# openmv.net
KiCad netlist of a schematic drawn in EAGLE
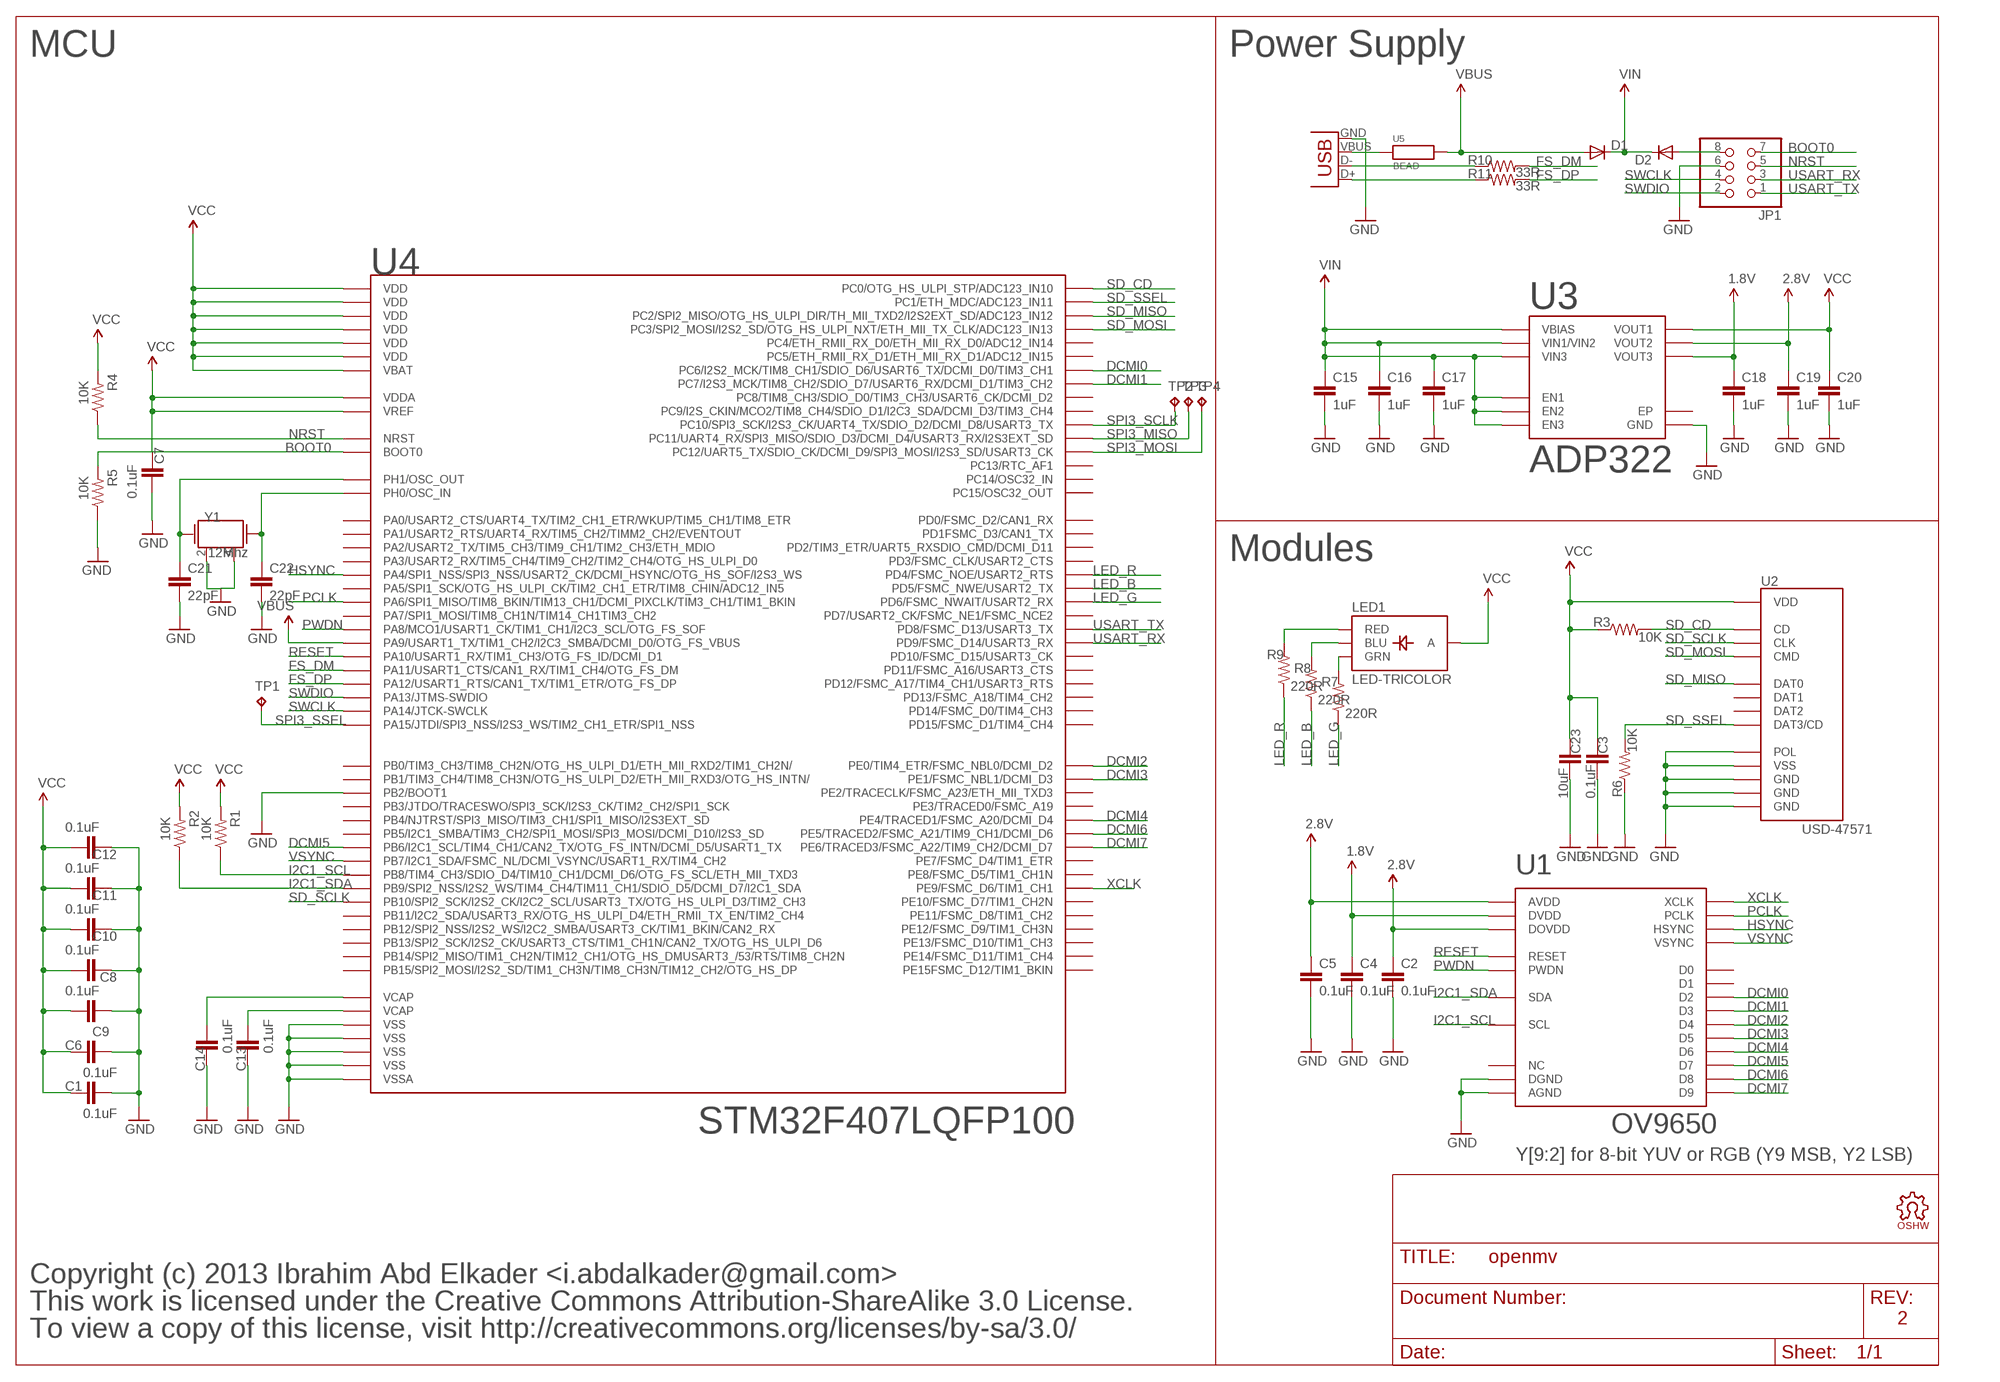
[diagram p0: schematic, sheet 1]

(export (version "E")
  (design (tool "Eeschema 10.0.6"))
  (components
    (comp (ref "C1")
      (value "0.1uF")
      (footprint "eagle-import:0402-CAP")
      (libsource (lib "eagle-import") (part "CAP0402-CAP"))
    )
    (comp (ref "C2")
      (value "0.1uF")
      (footprint "eagle-import:0402-CAP")
      (libsource (lib "eagle-import") (part "CAP0402-CAP"))
    )
    (comp (ref "C3")
      (value "0.1uF")
      (footprint "eagle-import:0402-CAP")
      (libsource (lib "eagle-import") (part "CAP0402-CAP"))
    )
    (comp (ref "C4")
      (value "0.1uF")
      (footprint "eagle-import:0402-CAP")
      (libsource (lib "eagle-import") (part "CAP0402-CAP"))
    )
    (comp (ref "C5")
      (value "0.1uF")
      (footprint "eagle-import:0402-CAP")
      (libsource (lib "eagle-import") (part "CAP0402-CAP"))
    )
    (comp (ref "C6")
      (value "0.1uF")
      (footprint "eagle-import:0402-CAP")
      (libsource (lib "eagle-import") (part "CAP0402-CAP"))
    )
    (comp (ref "C7")
      (value "0.1uF")
      (footprint "eagle-import:0402-CAP")
      (libsource (lib "eagle-import") (part "CAP0402-CAP"))
    )
    (comp (ref "C8")
      (value "0.1uF")
      (footprint "eagle-import:0402-CAP")
      (libsource (lib "eagle-import") (part "CAP0402-CAP"))
    )
    (comp (ref "C9")
      (value "0.1uF")
      (footprint "eagle-import:0402-CAP")
      (libsource (lib "eagle-import") (part "CAP0402-CAP"))
    )
    (comp (ref "C10")
      (value "0.1uF")
      (footprint "eagle-import:0402-CAP")
      (libsource (lib "eagle-import") (part "CAP0402-CAP"))
    )
    (comp (ref "C11")
      (value "0.1uF")
      (footprint "eagle-import:0402-CAP")
      (libsource (lib "eagle-import") (part "CAP0402-CAP"))
    )
    (comp (ref "C12")
      (value "0.1uF")
      (footprint "eagle-import:0402-CAP")
      (libsource (lib "eagle-import") (part "CAP0402-CAP"))
    )
    (comp (ref "C13")
      (value "0.1uF")
      (footprint "eagle-import:0402-CAP")
      (libsource (lib "eagle-import") (part "CAP0402-CAP"))
    )
    (comp (ref "C14")
      (value "0.1uF")
      (footprint "eagle-import:0402-CAP")
      (libsource (lib "eagle-import") (part "CAP0402-CAP"))
    )
    (comp (ref "C15")
      (value "1uF")
      (footprint "eagle-import:0402-CAP")
      (libsource (lib "eagle-import") (part "CAP0402-CAP"))
    )
    (comp (ref "C16")
      (value "1uF")
      (footprint "eagle-import:0402-CAP")
      (libsource (lib "eagle-import") (part "CAP0402-CAP"))
    )
    (comp (ref "C17")
      (value "1uF")
      (footprint "eagle-import:0402-CAP")
      (libsource (lib "eagle-import") (part "CAP0402-CAP"))
    )
    (comp (ref "C18")
      (value "1uF")
      (footprint "eagle-import:0402-CAP")
      (libsource (lib "eagle-import") (part "CAP0402-CAP"))
    )
    (comp (ref "C19")
      (value "1uF")
      (footprint "eagle-import:0402-CAP")
      (libsource (lib "eagle-import") (part "CAP0402-CAP"))
    )
    (comp (ref "C20")
      (value "1uF")
      (footprint "eagle-import:0402-CAP")
      (libsource (lib "eagle-import") (part "CAP0402-CAP"))
    )
    (comp (ref "C21")
      (value "22pF")
      (footprint "eagle-import:0402-CAP")
      (libsource (lib "eagle-import") (part "CAP0402-CAP"))
    )
    (comp (ref "C22")
      (value "22pF")
      (footprint "eagle-import:0402-CAP")
      (libsource (lib "eagle-import") (part "CAP0402-CAP"))
    )
    (comp (ref "C23")
      (value "10uF")
      (footprint "eagle-import:0805")
      (libsource (lib "eagle-import") (part "CAP0805"))
    )
    (comp (ref "D1")
      (value "DIODESOD")
      (footprint "eagle-import:SOD-323")
      (libsource (lib "eagle-import") (part "DIODESOD"))
    )
    (comp (ref "D2")
      (value "DIODESOD")
      (footprint "eagle-import:SOD-323")
      (libsource (lib "eagle-import") (part "DIODESOD"))
    )
    (comp (ref "JP1")
      (value "PINHD-2X4")
      (footprint "eagle-import:2X04")
      (libsource (lib "eagle-import") (part "PINHD-2X4"))
    )
    (comp (ref "LED1")
      (value "LED-TRICOLOR")
      (footprint "eagle-import:LED-TRICOLOR-SMD")
      (libsource (lib "eagle-import") (part "LED-TRICOLOR"))
    )
    (comp (ref "LOGO1")
      (value "OSHW_LOGO_FILLX0150-NT")
      (footprint "eagle-import:OSHW_FILLX150_NOTEXT")
      (libsource (lib "eagle-import") (part "OSHW_LOGO_FILLX0150-NT"))
    )
    (comp (ref "R1")
      (value "10K")
      (footprint "eagle-import:0402-RES")
      (libsource (lib "eagle-import") (part "RESISTOR0402-RES"))
    )
    (comp (ref "R2")
      (value "10K")
      (footprint "eagle-import:0402-RES")
      (libsource (lib "eagle-import") (part "RESISTOR0402-RES"))
    )
    (comp (ref "R3")
      (value "10K")
      (footprint "eagle-import:0402-RES")
      (libsource (lib "eagle-import") (part "RESISTOR0402-RES"))
    )
    (comp (ref "R4")
      (value "10K")
      (footprint "eagle-import:0402-RES")
      (libsource (lib "eagle-import") (part "RESISTOR0402-RES"))
    )
    (comp (ref "R5")
      (value "10K")
      (footprint "eagle-import:0402-RES")
      (libsource (lib "eagle-import") (part "RESISTOR0402-RES"))
    )
    (comp (ref "R6")
      (value "10K")
      (footprint "eagle-import:0402-RES")
      (libsource (lib "eagle-import") (part "RESISTOR0402-RES"))
    )
    (comp (ref "R7")
      (value "220R")
      (footprint "eagle-import:0402-RES")
      (libsource (lib "eagle-import") (part "RESISTOR0402-RES"))
    )
    (comp (ref "R8")
      (value "220R")
      (footprint "eagle-import:0402-RES")
      (libsource (lib "eagle-import") (part "RESISTOR0402-RES"))
    )
    (comp (ref "R9")
      (value "220R")
      (footprint "eagle-import:0402-RES")
      (libsource (lib "eagle-import") (part "RESISTOR0402-RES"))
    )
    (comp (ref "R10")
      (value "33R")
      (footprint "eagle-import:0402-RES")
      (libsource (lib "eagle-import") (part "RESISTOR0402-RES"))
    )
    (comp (ref "R11")
      (value "33R")
      (footprint "eagle-import:0402-RES")
      (libsource (lib "eagle-import") (part "RESISTOR0402-RES"))
    )
    (comp (ref "TP1")
      (value "TPTP10R")
      (footprint "eagle-import:TP10R")
      (libsource (lib "eagle-import") (part "TPTP10R"))
    )
    (comp (ref "TP2")
      (value "TPTP10R")
      (footprint "eagle-import:TP10R")
      (libsource (lib "eagle-import") (part "TPTP10R"))
    )
    (comp (ref "TP3")
      (value "TPTP10R")
      (footprint "eagle-import:TP10R")
      (libsource (lib "eagle-import") (part "TPTP10R"))
    )
    (comp (ref "TP4")
      (value "TPTP10R")
      (footprint "eagle-import:TP10R")
      (libsource (lib "eagle-import") (part "TPTP10R"))
    )
    (comp (ref "U1")
      (value "OV9650")
      (footprint "eagle-import:OV9650")
      (libsource (lib "eagle-import") (part "OV9650"))
    )
    (comp (ref "U2")
      (value "USD-47571")
      (footprint "eagle-import:USD-47571")
      (libsource (lib "eagle-import") (part "USD-47571"))
    )
    (comp (ref "U3")
      (value "ADP322")
      (footprint "eagle-import:WFQFN-16")
      (libsource (lib "eagle-import") (part "ADP322"))
    )
    (comp (ref "U4")
      (value "STM32F407LQFP100")
      (footprint "eagle-import:LQFP100")
      (libsource (lib "eagle-import") (part "STM32F407LQFP100"))
    )
    (comp (ref "U5")
      (value "BEAD")
      (footprint "eagle-import:0402-CAP")
      (libsource (lib "eagle-import") (part "BEAD"))
    )
    (comp (ref "X1")
      (value "USB-MICROB")
      (footprint "eagle-import:USB-MICROB")
      (libsource (lib "eagle-import") (part "USB-MICROB"))
    )
    (comp (ref "Y1")
      (value "12Mhz")
      (footprint "eagle-import:CRYSTAL-SMD-5X3")
      (libsource (lib "eagle-import") (part "CRYSTAL5X3"))
    )
  )
  (nets
    (net (code "1") (name "/BOOT0") (class "Default")
      (node (ref "JP1") (pin "7") (pinfunction "7_7") (pintype "passive"))
      (node (ref "R5") (pin "2") (pinfunction "2_2") (pintype "passive"))
      (node (ref "U4") (pin "94") (pinfunction "BOOT0_94") (pintype "bidirectional"))
    )
    (net (code "2") (name "/DCMI0") (class "Default")
      (node (ref "U1") (pin "P$19") (pinfunction "D2_P$19") (pintype "bidirectional"))
      (node (ref "U4") (pin "63") (pinfunction "PC6/I2S2_MCK/TIM8_CH1/SDIO_D6/USART6_TX/DCMI_D0/TIM3_CH1_63") (pintype "bidirectional"))
    )
    (net (code "3") (name "/DCMI1") (class "Default")
      (node (ref "U1") (pin "P$21") (pinfunction "D3_P$21") (pintype "bidirectional"))
      (node (ref "U4") (pin "64") (pinfunction "PC7/I2S3_MCK/TIM8_CH2/SDIO_D7/USART6_RX/DCMI_D1/TIM3_CH2_64") (pintype "bidirectional"))
    )
    (net (code "4") (name "/DCMI2") (class "Default")
      (node (ref "U1") (pin "P$22") (pinfunction "D4_P$22") (pintype "bidirectional"))
      (node (ref "U4") (pin "97") (pinfunction "PE0/TIM4_ETR/FSMC_NBL0/DCMI_D2_97") (pintype "bidirectional"))
    )
    (net (code "5") (name "/DCMI3") (class "Default")
      (node (ref "U1") (pin "P$20") (pinfunction "D5_P$20") (pintype "bidirectional"))
      (node (ref "U4") (pin "98") (pinfunction "PE1/FSMC_NBL1/DCMI_D3_98") (pintype "bidirectional"))
    )
    (net (code "6") (name "/DCMI4") (class "Default")
      (node (ref "U1") (pin "P$18") (pinfunction "D6_P$18") (pintype "bidirectional"))
      (node (ref "U4") (pin "3") (pinfunction "PE4/TRACED1/FSMC_A20/DCMI_D4_3") (pintype "bidirectional"))
    )
    (net (code "7") (name "/DCMI5") (class "Default")
      (node (ref "U1") (pin "P$16") (pinfunction "D7_P$16") (pintype "bidirectional"))
      (node (ref "U4") (pin "92") (pinfunction "PB6/I2C1_SCL/TIM4_CH1/CAN2_TX/OTG_FS_INTN/DCMI_D5/USART1_TX_92") (pintype "bidirectional"))
    )
    (net (code "8") (name "/DCMI6") (class "Default")
      (node (ref "U1") (pin "P$14") (pinfunction "D8_P$14") (pintype "bidirectional"))
      (node (ref "U4") (pin "4") (pinfunction "PE5/TRACED2/FSMC_A21/TIM9_CH1/DCMI_D6_4") (pintype "bidirectional"))
    )
    (net (code "9") (name "/DCMI7") (class "Default")
      (node (ref "U1") (pin "P$12") (pinfunction "D9_P$12") (pintype "bidirectional"))
      (node (ref "U4") (pin "5") (pinfunction "PE6/TRACED3/FSMC_A22/TIM9_CH2/DCMI_D7_5") (pintype "bidirectional"))
    )
    (net (code "10") (name "/FS_DM") (class "Default")
      (node (ref "R10") (pin "2") (pinfunction "2_2") (pintype "passive"))
      (node (ref "U4") (pin "70") (pinfunction "PA11/USART1_CTS/CAN1_RX/TIM1_CH4/OTG_FS_DM_70") (pintype "bidirectional"))
    )
    (net (code "11") (name "/FS_DP") (class "Default")
      (node (ref "R11") (pin "2") (pinfunction "2_2") (pintype "passive"))
      (node (ref "U4") (pin "71") (pinfunction "PA12/USART1_RTS/CAN1_TX/TIM1_ETR/OTG_FS_DP_71") (pintype "bidirectional"))
    )
    (net (code "12") (name "/HSYNC") (class "Default")
      (node (ref "U1") (pin "P$9") (pinfunction "HSYNC_P$9") (pintype "bidirectional"))
      (node (ref "U4") (pin "29") (pinfunction "PA4/SPI1_NSS/SPI3_NSS/USART2_CK/DCMI_HSYNC/OTG_HS_SOF/I2S3_WS_29") (pintype "bidirectional"))
    )
    (net (code "13") (name "/I2C1_SCL") (class "Default")
      (node (ref "R1") (pin "1") (pinfunction "1_1") (pintype "passive"))
      (node (ref "U1") (pin "P$5") (pinfunction "SCL_P$5") (pintype "bidirectional"))
      (node (ref "U4") (pin "95") (pinfunction "PB8/TIM4_CH3/SDIO_D4/TIM10_CH1/DCMI_D6/OTG_FS_SCL/ETH_MII_TXD3_95") (pintype "bidirectional"))
    )
    (net (code "14") (name "/I2C1_SDA") (class "Default")
      (node (ref "R2") (pin "1") (pinfunction "1_1") (pintype "passive"))
      (node (ref "U1") (pin "P$3") (pinfunction "SDA_P$3") (pintype "bidirectional"))
      (node (ref "U4") (pin "96") (pinfunction "PB9/SPI2_NSS/I2S2_WS/TIM4_CH4/TIM11_CH1/SDIO_D5/DCMI_D7/I2C1_SDA_96") (pintype "bidirectional"))
    )
    (net (code "15") (name "/LED_B") (class "Default")
      (node (ref "R8") (pin "1") (pinfunction "1_1") (pintype "passive"))
      (node (ref "U4") (pin "86") (pinfunction "PD5/FSMC_NWE/USART2_TX_86") (pintype "bidirectional"))
    )
    (net (code "16") (name "/LED_G") (class "Default")
      (node (ref "R7") (pin "1") (pinfunction "1_1") (pintype "passive"))
      (node (ref "U4") (pin "87") (pinfunction "PD6/FSMC_NWAIT/USART2_RX_87") (pintype "bidirectional"))
    )
    (net (code "17") (name "/LED_R") (class "Default")
      (node (ref "R9") (pin "1") (pinfunction "1_1") (pintype "passive"))
      (node (ref "U4") (pin "85") (pinfunction "PD4/FSMC_NOE/USART2_RTS_85") (pintype "bidirectional"))
    )
    (net (code "18") (name "/NRST") (class "Default")
      (node (ref "JP1") (pin "5") (pinfunction "5_5") (pintype "passive"))
      (node (ref "R4") (pin "1") (pinfunction "1_1") (pintype "passive"))
      (node (ref "U4") (pin "14") (pinfunction "NRST_14") (pintype "bidirectional"))
    )
    (net (code "19") (name "/PCLK") (class "Default")
      (node (ref "U1") (pin "P$17") (pinfunction "PCLK_P$17") (pintype "bidirectional"))
      (node (ref "U4") (pin "31") (pinfunction "PA6/SPI1_MISO/TIM8_BKIN/TIM13_CH1/DCMI_PIXCLK/TIM3_CH1/TIM1_BKIN_31") (pintype "bidirectional"))
    )
    (net (code "20") (name "/PWDN") (class "Default")
      (node (ref "U1") (pin "P$8") (pinfunction "PWDN_P$8") (pintype "bidirectional"))
      (node (ref "U4") (pin "67") (pinfunction "PA8/MCO1/USART1_CK/TIM1_CH1/I2C3_SCL/OTG_FS_SOF_67") (pintype "bidirectional"))
    )
    (net (code "21") (name "/RESET") (class "Default")
      (node (ref "U1") (pin "P$6") (pinfunction "RESET_P$6") (pintype "bidirectional"))
      (node (ref "U4") (pin "69") (pinfunction "PA10/USART1_RX/TIM1_CH3/OTG_FS_ID/DCMI_D1_69") (pintype "bidirectional"))
    )
    (net (code "22") (name "/SD_CD") (class "Default")
      (node (ref "R3") (pin "2") (pinfunction "2_2") (pintype "passive"))
      (node (ref "U2") (pin "G$5") (pinfunction "CD_G$5") (pintype "power_in"))
      (node (ref "U4") (pin "15") (pinfunction "PC0/OTG_HS_ULPI_STP/ADC123_IN10_15") (pintype "bidirectional"))
    )
    (net (code "23") (name "/SD_MISO") (class "Default")
      (node (ref "U2") (pin "P$7") (pinfunction "DAT0_P$7") (pintype "bidirectional"))
      (node (ref "U4") (pin "17") (pinfunction "PC2/SPI2_MISO/OTG_HS_ULPI_DIR/TH_MII_TXD2/I2S2EXT_SD/ADC123_IN12_17") (pintype "bidirectional"))
    )
    (net (code "24") (name "/SD_MOSI") (class "Default")
      (node (ref "U2") (pin "P$3") (pinfunction "CMD_P$3") (pintype "bidirectional"))
      (node (ref "U4") (pin "18") (pinfunction "PC3/SPI2_MOSI/I2S2_SD/OTG_HS_ULPI_NXT/ETH_MII_TX_CLK/ADC123_IN13_18") (pintype "bidirectional"))
    )
    (net (code "25") (name "/SD_SCLK") (class "Default")
      (node (ref "U2") (pin "P$5") (pinfunction "CLK_P$5") (pintype "bidirectional"))
      (node (ref "U4") (pin "47") (pinfunction "PB10/SPI2_SCK/I2S2_CK/I2C2_SCL/USART3_TX/OTG_HS_ULPI_D3/TIM2_CH3_47") (pintype "bidirectional"))
    )
    (net (code "26") (name "/SD_SSEL") (class "Default")
      (node (ref "R6") (pin "2") (pinfunction "2_2") (pintype "passive"))
      (node (ref "U2") (pin "P$2") (pinfunction "DAT3/CD_P$2") (pintype "bidirectional"))
      (node (ref "U4") (pin "16") (pinfunction "PC1/ETH_MDC/ADC123_IN11_16") (pintype "bidirectional"))
    )
    (net (code "27") (name "/SPI3_MISO") (class "Default")
      (node (ref "TP3") (pin "TP") (pinfunction "TP_TP") (pintype "input"))
      (node (ref "U4") (pin "79") (pinfunction "PC11/UART4_RX/SPI3_MISO/SDIO_D3/DCMI_D4/USART3_RX/I2S3EXT_SD_79") (pintype "bidirectional"))
    )
    (net (code "28") (name "/SPI3_MOSI") (class "Default")
      (node (ref "TP4") (pin "TP") (pinfunction "TP_TP") (pintype "input"))
      (node (ref "U4") (pin "80") (pinfunction "PC12/UART5_TX/SDIO_CK/DCMI_D9/SPI3_MOSI/I2S3_SD/USART3_CK_80") (pintype "bidirectional"))
    )
    (net (code "29") (name "/SPI3_SCLK") (class "Default")
      (node (ref "TP2") (pin "TP") (pinfunction "TP_TP") (pintype "input"))
      (node (ref "U4") (pin "78") (pinfunction "PC10/SPI3_SCK/I2S3_CK/UART4_TX/SDIO_D2/DCMI_D8/USART3_TX_78") (pintype "bidirectional"))
    )
    (net (code "30") (name "/SPI3_SSEL") (class "Default")
      (node (ref "TP1") (pin "TP") (pinfunction "TP_TP") (pintype "input"))
      (node (ref "U4") (pin "77") (pinfunction "PA15/JTDI/SPI3_NSS/I2S3_WS/TIM2_CH1_ETR/SPI1_NSS_77") (pintype "bidirectional"))
    )
    (net (code "31") (name "/SWCLK") (class "Default")
      (node (ref "JP1") (pin "4") (pinfunction "4_4") (pintype "passive"))
      (node (ref "U4") (pin "76") (pinfunction "PA14/JTCK-SWCLK_76") (pintype "bidirectional"))
    )
    (net (code "32") (name "/SWDIO") (class "Default")
      (node (ref "JP1") (pin "2") (pinfunction "2_2") (pintype "passive"))
      (node (ref "U4") (pin "72") (pinfunction "PA13/JTMS-SWDIO_72") (pintype "bidirectional"))
    )
    (net (code "33") (name "/USART_RX") (class "Default")
      (node (ref "JP1") (pin "3") (pinfunction "3_3") (pintype "passive"))
      (node (ref "U4") (pin "56") (pinfunction "PD9/FSMC_D14/USART3_RX_56") (pintype "bidirectional"))
    )
    (net (code "34") (name "/USART_TX") (class "Default")
      (node (ref "JP1") (pin "1") (pinfunction "1_1") (pintype "passive"))
      (node (ref "U4") (pin "55") (pinfunction "PD8/FSMC_D13/USART3_TX_55") (pintype "bidirectional"))
    )
    (net (code "35") (name "/VSYNC") (class "Default")
      (node (ref "U1") (pin "P$7") (pinfunction "VSYNC_P$7") (pintype "bidirectional"))
      (node (ref "U4") (pin "93") (pinfunction "PB7/I2C1_SDA/FSMC_NL/DCMI_VSYNC/USART1_RX/TIM4_CH2_93") (pintype "bidirectional"))
    )
    (net (code "36") (name "/XCLK") (class "Default")
      (node (ref "U1") (pin "P$13") (pinfunction "XCLK_P$13") (pintype "bidirectional"))
      (node (ref "U4") (pin "40") (pinfunction "PE9/FSMC_D6/TIM1_CH1_40") (pintype "bidirectional"))
    )
    (net (code "37") (name "1.8V") (class "Default")
      (node (ref "C18") (pin "1") (pinfunction "1_1") (pintype "passive"))
      (node (ref "C4") (pin "1") (pinfunction "1_1") (pintype "passive"))
      (node (ref "U1") (pin "P$10") (pinfunction "DVDD_P$10") (pintype "bidirectional"))
      (node (ref "U3") (pin "8") (pinfunction "VOUT3_8") (pintype "passive"))
    )
    (net (code "38") (name "2.8V") (class "Default")
      (node (ref "C19") (pin "1") (pinfunction "1_1") (pintype "passive"))
      (node (ref "C2") (pin "1") (pinfunction "1_1") (pintype "passive"))
      (node (ref "C5") (pin "1") (pinfunction "1_1") (pintype "passive"))
      (node (ref "U1") (pin "P$11") (pinfunction "DOVDD_P$11") (pintype "bidirectional"))
      (node (ref "U1") (pin "P$4") (pinfunction "AVDD_P$4") (pintype "power_in"))
      (node (ref "U3") (pin "6") (pinfunction "VOUT2_6") (pintype "passive"))
    )
    (net (code "39") (name "GND") (class "Default")
      (node (ref "C1") (pin "1") (pinfunction "1_1") (pintype "passive"))
      (node (ref "C10") (pin "2") (pinfunction "2_2") (pintype "passive"))
      (node (ref "C11") (pin "2") (pinfunction "2_2") (pintype "passive"))
      (node (ref "C12") (pin "2") (pinfunction "2_2") (pintype "passive"))
      (node (ref "C13") (pin "2") (pinfunction "2_2") (pintype "passive"))
      (node (ref "C14") (pin "2") (pinfunction "2_2") (pintype "passive"))
      (node (ref "C15") (pin "2") (pinfunction "2_2") (pintype "passive"))
      (node (ref "C16") (pin "2") (pinfunction "2_2") (pintype "passive"))
      (node (ref "C17") (pin "2") (pinfunction "2_2") (pintype "passive"))
      (node (ref "C18") (pin "2") (pinfunction "2_2") (pintype "passive"))
      (node (ref "C19") (pin "2") (pinfunction "2_2") (pintype "passive"))
      (node (ref "C2") (pin "2") (pinfunction "2_2") (pintype "passive"))
      (node (ref "C20") (pin "2") (pinfunction "2_2") (pintype "passive"))
      (node (ref "C21") (pin "2") (pinfunction "2_2") (pintype "passive"))
      (node (ref "C22") (pin "2") (pinfunction "2_2") (pintype "passive"))
      (node (ref "C23") (pin "2") (pinfunction "2_2") (pintype "passive"))
      (node (ref "C3") (pin "2") (pinfunction "2_2") (pintype "passive"))
      (node (ref "C4") (pin "2") (pinfunction "2_2") (pintype "passive"))
      (node (ref "C5") (pin "2") (pinfunction "2_2") (pintype "passive"))
      (node (ref "C6") (pin "1") (pinfunction "1_1") (pintype "passive"))
      (node (ref "C7") (pin "1") (pinfunction "1_1") (pintype "passive"))
      (node (ref "C8") (pin "2") (pinfunction "2_2") (pintype "passive"))
      (node (ref "C9") (pin "1") (pinfunction "1_1") (pintype "passive"))
      (node (ref "JP1") (pin "6") (pinfunction "6_6") (pintype "passive"))
      (node (ref "R5") (pin "1") (pinfunction "1_1") (pintype "passive"))
      (node (ref "R6") (pin "1") (pinfunction "1_1") (pintype "passive"))
      (node (ref "U1") (pin "P$15") (pinfunction "DGND_P$15") (pintype "bidirectional"))
      (node (ref "U1") (pin "P$2") (pinfunction "AGND_P$2") (pintype "power_in"))
      (node (ref "U2") (pin "G$1") (pinfunction "GND_G$1") (pintype "power_in"))
      (node (ref "U2") (pin "G$2") (pinfunction "GND_G$2") (pintype "power_in"))
      (node (ref "U2") (pin "G$3") (pinfunction "GND_G$3") (pintype "power_in"))
      (node (ref "U2") (pin "G$4") (pinfunction "POL_G$4") (pintype "power_in"))
      (node (ref "U2") (pin "P$6") (pinfunction "VSS_P$6") (pintype "power_in"))
      (node (ref "U3") (pin "12") (pinfunction "GND_12") (pintype "power_in"))
      (node (ref "U4") (pin "10") (pinfunction "VSS_10") (pintype "power_in"))
      (node (ref "U4") (pin "20") (pinfunction "VSSA_20") (pintype "power_in"))
      (node (ref "U4") (pin "27") (pinfunction "VSS_27") (pintype "power_in"))
      (node (ref "U4") (pin "37") (pinfunction "PB2/BOOT1_37") (pintype "bidirectional"))
      (node (ref "U4") (pin "74") (pinfunction "VSS_74") (pintype "power_in"))
      (node (ref "U4") (pin "99") (pinfunction "VSS_99") (pintype "power_in"))
      (node (ref "X1") (pin "GND") (pinfunction "GND_GND") (pintype "bidirectional"))
      (node (ref "Y1") (pin "2") (pinfunction "P$1_2") (pintype "power_in"))
      (node (ref "Y1") (pin "4") (pinfunction "P$2_4") (pintype "power_in"))
    )
    (net (code "40") (name "Net-(C13-Pad1)") (class "Default")
      (node (ref "C13") (pin "1") (pinfunction "1_1") (pintype "passive"))
      (node (ref "U4") (pin "73") (pinfunction "VCAP_73") (pintype "power_in"))
    )
    (net (code "41") (name "Net-(C14-Pad1)") (class "Default")
      (node (ref "C14") (pin "1") (pinfunction "1_1") (pintype "passive"))
      (node (ref "U4") (pin "49") (pinfunction "VCAP_49") (pintype "power_in"))
    )
    (net (code "42") (name "Net-(D2-A)") (class "Default")
      (node (ref "D2") (pin "2") (pinfunction "A_2") (pintype "passive"))
      (node (ref "JP1") (pin "8") (pinfunction "8_8") (pintype "passive"))
    )
    (net (code "43") (name "Net-(LED1-BLU)") (class "Default")
      (node (ref "LED1") (pin "B") (pinfunction "BLU_B") (pintype "bidirectional"))
      (node (ref "R8") (pin "2") (pinfunction "2_2") (pintype "passive"))
    )
    (net (code "44") (name "Net-(LED1-GRN)") (class "Default")
      (node (ref "LED1") (pin "G") (pinfunction "GRN_G") (pintype "bidirectional"))
      (node (ref "R7") (pin "2") (pinfunction "2_2") (pintype "passive"))
    )
    (net (code "45") (name "Net-(LED1-RED)") (class "Default")
      (node (ref "LED1") (pin "R") (pinfunction "RED_R") (pintype "bidirectional"))
      (node (ref "R9") (pin "2") (pinfunction "2_2") (pintype "passive"))
    )
    (net (code "46") (name "Net-(R10-Pad1)") (class "Default")
      (node (ref "R10") (pin "1") (pinfunction "1_1") (pintype "passive"))
      (node (ref "X1") (pin "D-") (pinfunction "D-_D-") (pintype "bidirectional"))
    )
    (net (code "47") (name "Net-(R11-Pad1)") (class "Default")
      (node (ref "R11") (pin "1") (pinfunction "1_1") (pintype "passive"))
      (node (ref "X1") (pin "D+") (pinfunction "D+_D+") (pintype "bidirectional"))
    )
    (net (code "48") (name "Net-(U4-PH0{slash}OSC_IN)") (class "Default")
      (node (ref "C22") (pin "1") (pinfunction "1_1") (pintype "passive"))
      (node (ref "U4") (pin "12") (pinfunction "PH0/OSC_IN_12") (pintype "bidirectional"))
      (node (ref "Y1") (pin "3") (pinfunction "2_3") (pintype "passive"))
    )
    (net (code "49") (name "Net-(U4-PH1{slash}OSC_OUT)") (class "Default")
      (node (ref "C21") (pin "1") (pinfunction "1_1") (pintype "passive"))
      (node (ref "U4") (pin "13") (pinfunction "PH1/OSC_OUT_13") (pintype "bidirectional"))
      (node (ref "Y1") (pin "1") (pinfunction "1_1") (pintype "passive"))
    )
    (net (code "50") (name "Net-(U5-Pad1)") (class "Default")
      (node (ref "U5") (pin "1") (pinfunction "1_1") (pintype "passive"))
      (node (ref "X1") (pin "VBUS") (pinfunction "VBUS_VBUS") (pintype "bidirectional"))
    )
    (net (code "51") (name "VBUS") (class "Default")
      (node (ref "D1") (pin "2") (pinfunction "A_2") (pintype "passive"))
      (node (ref "U4") (pin "68") (pinfunction "PA9/USART1_TX/TIM1_CH2/I2C3_SMBA/DCMI_D0/OTG_FS_VBUS_68") (pintype "bidirectional"))
      (node (ref "U5") (pin "2") (pinfunction "2_2") (pintype "passive"))
    )
    (net (code "52") (name "VCC") (class "Default")
      (node (ref "C1") (pin "2") (pinfunction "2_2") (pintype "passive"))
      (node (ref "C10") (pin "1") (pinfunction "1_1") (pintype "passive"))
      (node (ref "C11") (pin "1") (pinfunction "1_1") (pintype "passive"))
      (node (ref "C12") (pin "1") (pinfunction "1_1") (pintype "passive"))
      (node (ref "C20") (pin "1") (pinfunction "1_1") (pintype "passive"))
      (node (ref "C23") (pin "1") (pinfunction "1_1") (pintype "passive"))
      (node (ref "C3") (pin "1") (pinfunction "1_1") (pintype "passive"))
      (node (ref "C6") (pin "2") (pinfunction "2_2") (pintype "passive"))
      (node (ref "C7") (pin "2") (pinfunction "2_2") (pintype "passive"))
      (node (ref "C8") (pin "1") (pinfunction "1_1") (pintype "passive"))
      (node (ref "C9") (pin "2") (pinfunction "2_2") (pintype "passive"))
      (node (ref "LED1") (pin "A") (pinfunction "A_A") (pintype "bidirectional"))
      (node (ref "R1") (pin "2") (pinfunction "2_2") (pintype "passive"))
      (node (ref "R2") (pin "2") (pinfunction "2_2") (pintype "passive"))
      (node (ref "R3") (pin "1") (pinfunction "1_1") (pintype "passive"))
      (node (ref "R4") (pin "2") (pinfunction "2_2") (pintype "passive"))
      (node (ref "U2") (pin "P$4") (pinfunction "VDD_P$4") (pintype "power_in"))
      (node (ref "U3") (pin "5") (pinfunction "VOUT1_5") (pintype "passive"))
      (node (ref "U4") (pin "100") (pinfunction "VDD_100") (pintype "power_in"))
      (node (ref "U4") (pin "11") (pinfunction "VDD_11") (pintype "power_in"))
      (node (ref "U4") (pin "19") (pinfunction "VDD_19") (pintype "power_in"))
      (node (ref "U4") (pin "21") (pinfunction "VREF_21") (pintype "power_in"))
      (node (ref "U4") (pin "22") (pinfunction "VDDA_22") (pintype "power_in"))
      (node (ref "U4") (pin "28") (pinfunction "VDD_28") (pintype "power_in"))
      (node (ref "U4") (pin "50") (pinfunction "VDD_50") (pintype "power_in"))
      (node (ref "U4") (pin "6") (pinfunction "VBAT_6") (pintype "power_in"))
      (node (ref "U4") (pin "75") (pinfunction "VDD_75") (pintype "power_in"))
    )
    (net (code "53") (name "VIN") (class "Default")
      (node (ref "C15") (pin "1") (pinfunction "1_1") (pintype "passive"))
      (node (ref "C16") (pin "1") (pinfunction "1_1") (pintype "passive"))
      (node (ref "C17") (pin "1") (pinfunction "1_1") (pintype "passive"))
      (node (ref "D1") (pin "1") (pinfunction "C_1") (pintype "passive"))
      (node (ref "D2") (pin "1") (pinfunction "C_1") (pintype "passive"))
      (node (ref "U3") (pin "1") (pinfunction "EN1_1") (pintype "passive"))
      (node (ref "U3") (pin "10") (pinfunction "VIN3_10") (pintype "power_in"))
      (node (ref "U3") (pin "15") (pinfunction "EN3_15") (pintype "passive"))
      (node (ref "U3") (pin "16") (pinfunction "EN2_16") (pintype "passive"))
      (node (ref "U3") (pin "2") (pinfunction "VBIAS_2") (pintype "power_in"))
      (node (ref "U3") (pin "3") (pinfunction "VIN1/VIN2_3") (pintype "power_in"))
    )
    (net (code "54") (name "unconnected-(U1-D0-PadP$24)") (class "Default")
      (node (ref "U1") (pin "P$24") (pinfunction "D0_P$24") (pintype "bidirectional"))
    )
    (net (code "55") (name "unconnected-(U1-D1-PadP$23)") (class "Default")
      (node (ref "U1") (pin "P$23") (pinfunction "D1_P$23") (pintype "bidirectional"))
    )
    (net (code "56") (name "unconnected-(U1-NC-PadP$1)") (class "Default")
      (node (ref "U1") (pin "P$1") (pinfunction "NC_P$1") (pintype "no_connect"))
    )
    (net (code "57") (name "unconnected-(U2-DAT1-PadP$8)") (class "Default")
      (node (ref "U2") (pin "P$8") (pinfunction "DAT1_P$8") (pintype "bidirectional"))
    )
    (net (code "58") (name "unconnected-(U2-DAT2-PadP$1)") (class "Default")
      (node (ref "U2") (pin "P$1") (pinfunction "DAT2_P$1") (pintype "bidirectional"))
    )
    (net (code "59") (name "unconnected-(U3A-EP-PadEXP)") (class "Default")
      (node (ref "U3") (pin "EXP") (pinfunction "EP_EXP") (pintype "input"))
    )
    (net (code "60") (name "unconnected-(U4-PA0{slash}USART2_CTS{slash}UART4_TX{slash}TIM2_CH1_ETR{slash}WKUP{slash}TIM5_CH1{slash}TIM8_ETR-Pad23)") (class "Default")
      (node (ref "U4") (pin "23") (pinfunction "PA0/USART2_CTS/UART4_TX/TIM2_CH1_ETR/WKUP/TIM5_CH1/TIM8_ETR_23") (pintype "bidirectional"))
    )
    (net (code "61") (name "unconnected-(U4-PA1{slash}USART2_RTS{slash}UART4_RX{slash}TIM5_CH2{slash}TIMM2_CH2{slash}EVENTOUT-Pad24)") (class "Default")
      (node (ref "U4") (pin "24") (pinfunction "PA1/USART2_RTS/UART4_RX/TIM5_CH2/TIMM2_CH2/EVENTOUT_24") (pintype "bidirectional"))
    )
    (net (code "62") (name "unconnected-(U4-PA2{slash}USART2_TX{slash}TIM5_CH3{slash}TIM9_CH1{slash}TIM2_CH3{slash}ETH_MDIO-Pad25)") (class "Default")
      (node (ref "U4") (pin "25") (pinfunction "PA2/USART2_TX/TIM5_CH3/TIM9_CH1/TIM2_CH3/ETH_MDIO_25") (pintype "bidirectional"))
    )
    (net (code "63") (name "unconnected-(U4-PA3{slash}USART2_RX{slash}TIM5_CH4{slash}TIM9_CH2{slash}TIM2_CH4{slash}OTG_HS_ULPI_D0-Pad26)") (class "Default")
      (node (ref "U4") (pin "26") (pinfunction "PA3/USART2_RX/TIM5_CH4/TIM9_CH2/TIM2_CH4/OTG_HS_ULPI_D0_26") (pintype "bidirectional"))
    )
    (net (code "64") (name "unconnected-(U4-PA5{slash}SPI1_SCK{slash}OTG_HS_ULPI_CK{slash}TIM2_CH1_ETR{slash}TIM8_CHIN{slash}ADC12_IN5-Pad30)") (class "Default")
      (node (ref "U4") (pin "30") (pinfunction "PA5/SPI1_SCK/OTG_HS_ULPI_CK/TIM2_CH1_ETR/TIM8_CHIN/ADC12_IN5_30") (pintype "bidirectional"))
    )
    (net (code "65") (name "unconnected-(U4-PA7{slash}SPI1_MOSI{slash}TIM8_CH1N{slash}TIM14_CH1TIM3_CH2-Pad32)") (class "Default")
      (node (ref "U4") (pin "32") (pinfunction "PA7/SPI1_MOSI/TIM8_CH1N/TIM14_CH1TIM3_CH2_32") (pintype "bidirectional"))
    )
    (net (code "66") (name "unconnected-(U4-PB0{slash}TIM3_CH3{slash}TIM8_CH2N{slash}OTG_HS_ULPI_D1{slash}ETH_MII_RXD2{slash}TIM1_CH2N{slash}-Pad35)") (class "Default")
      (node (ref "U4") (pin "35") (pinfunction "PB0/TIM3_CH3/TIM8_CH2N/OTG_HS_ULPI_D1/ETH_MII_RXD2/TIM1_CH2N/_35") (pintype "bidirectional"))
    )
    (net (code "67") (name "unconnected-(U4-PB1{slash}TIM3_CH4{slash}TIM8_CH3N{slash}OTG_HS_ULPI_D2{slash}ETH_MII_RXD3{slash}OTG_HS_INTN{slash}-Pad36)") (class "Default")
      (node (ref "U4") (pin "36") (pinfunction "PB1/TIM3_CH4/TIM8_CH3N/OTG_HS_ULPI_D2/ETH_MII_RXD3/OTG_HS_INTN/_36") (pintype "bidirectional"))
    )
    (net (code "68") (name "unconnected-(U4-PB3{slash}JTDO{slash}TRACESWO{slash}SPI3_SCK{slash}I2S3_CK{slash}TIM2_CH2{slash}SPI1_SCK-Pad89)") (class "Default")
      (node (ref "U4") (pin "89") (pinfunction "PB3/JTDO/TRACESWO/SPI3_SCK/I2S3_CK/TIM2_CH2/SPI1_SCK_89") (pintype "bidirectional"))
    )
    (net (code "69") (name "unconnected-(U4-PB4{slash}NJTRST{slash}SPI3_MISO{slash}TIM3_CH1{slash}SPI1_MISO{slash}I2S3EXT_SD-Pad90)") (class "Default")
      (node (ref "U4") (pin "90") (pinfunction "PB4/NJTRST/SPI3_MISO/TIM3_CH1/SPI1_MISO/I2S3EXT_SD_90") (pintype "bidirectional"))
    )
    (net (code "70") (name "unconnected-(U4-PB5{slash}I2C1_SMBA{slash}TIM3_CH2{slash}SPI1_MOSI{slash}SPI3_MOSI{slash}DCMI_D10{slash}I2S3_SD-Pad91)") (class "Default")
      (node (ref "U4") (pin "91") (pinfunction "PB5/I2C1_SMBA/TIM3_CH2/SPI1_MOSI/SPI3_MOSI/DCMI_D10/I2S3_SD_91") (pintype "bidirectional"))
    )
    (net (code "71") (name "unconnected-(U4-PB11{slash}I2C2_SDA{slash}USART3_RX{slash}OTG_HS_ULPI_D4{slash}ETH_RMII_TX_EN{slash}TIM2_CH4-Pad48)") (class "Default")
      (node (ref "U4") (pin "48") (pinfunction "PB11/I2C2_SDA/USART3_RX/OTG_HS_ULPI_D4/ETH_RMII_TX_EN/TIM2_CH4_48") (pintype "bidirectional"))
    )
    (net (code "72") (name "unconnected-(U4-PB12{slash}SPI2_NSS{slash}I2S2_WS{slash}I2C2_SMBA{slash}USART3_CK{slash}TIM1_BKIN{slash}CAN2_RX-Pad51)") (class "Default")
      (node (ref "U4") (pin "51") (pinfunction "PB12/SPI2_NSS/I2S2_WS/I2C2_SMBA/USART3_CK/TIM1_BKIN/CAN2_RX_51") (pintype "bidirectional"))
    )
    (net (code "73") (name "unconnected-(U4-PB13{slash}SPI2_SCK{slash}I2S2_CK{slash}USART3_CTS{slash}TIM1_CH1N{slash}CAN2_TX{slash}OTG_HS_ULPI_D6-Pad52)") (class "Default")
      (node (ref "U4") (pin "52") (pinfunction "PB13/SPI2_SCK/I2S2_CK/USART3_CTS/TIM1_CH1N/CAN2_TX/OTG_HS_ULPI_D6_52") (pintype "bidirectional"))
    )
    (net (code "74") (name "unconnected-(U4-PB14{slash}SPI2_MISO{slash}TIM1_CH2N{slash}TIM12_CH1{slash}OTG_HS_DMUSART3_{slash}53{slash}RTS{slash}TIM8_CH2N-Pad53)") (class "Default")
      (node (ref "U4") (pin "53") (pinfunction "PB14/SPI2_MISO/TIM1_CH2N/TIM12_CH1/OTG_HS_DMUSART3_/53/RTS/TIM8_CH2N_53") (pintype "bidirectional"))
    )
    (net (code "75") (name "unconnected-(U4-PB15{slash}SPI2_MOSI{slash}I2S2_SD{slash}TIM1_CH3N{slash}TIM8_CH3N{slash}TIM12_CH2{slash}OTG_HS_DP-Pad54)") (class "Default")
      (node (ref "U4") (pin "54") (pinfunction "PB15/SPI2_MOSI/I2S2_SD/TIM1_CH3N/TIM8_CH3N/TIM12_CH2/OTG_HS_DP_54") (pintype "bidirectional"))
    )
    (net (code "76") (name "unconnected-(U4-PC4{slash}ETH_RMII_RX_D0{slash}ETH_MII_RX_D0{slash}ADC12_IN14-Pad33)") (class "Default")
      (node (ref "U4") (pin "33") (pinfunction "PC4/ETH_RMII_RX_D0/ETH_MII_RX_D0/ADC12_IN14_33") (pintype "bidirectional"))
    )
    (net (code "77") (name "unconnected-(U4-PC5{slash}ETH_RMII_RX_D1{slash}ETH_MII_RX_D1{slash}ADC12_IN15-Pad34)") (class "Default")
      (node (ref "U4") (pin "34") (pinfunction "PC5/ETH_RMII_RX_D1/ETH_MII_RX_D1/ADC12_IN15_34") (pintype "bidirectional"))
    )
    (net (code "78") (name "unconnected-(U4-PC8{slash}TIM8_CH3{slash}SDIO_D0{slash}TIM3_CH3{slash}USART6_CK{slash}DCMI_D2-Pad65)") (class "Default")
      (node (ref "U4") (pin "65") (pinfunction "PC8/TIM8_CH3/SDIO_D0/TIM3_CH3/USART6_CK/DCMI_D2_65") (pintype "bidirectional"))
    )
    (net (code "79") (name "unconnected-(U4-PC9{slash}I2S_CKIN{slash}MCO2{slash}TIM8_CH4{slash}SDIO_D1{slash}I2C3_SDA{slash}DCMI_D3{slash}TIM3_CH4-Pad66)") (class "Default")
      (node (ref "U4") (pin "66") (pinfunction "PC9/I2S_CKIN/MCO2/TIM8_CH4/SDIO_D1/I2C3_SDA/DCMI_D3/TIM3_CH4_66") (pintype "bidirectional"))
    )
    (net (code "80") (name "unconnected-(U4-PC13{slash}RTC_AF1-Pad7)") (class "Default")
      (node (ref "U4") (pin "7") (pinfunction "PC13/RTC_AF1_7") (pintype "bidirectional"))
    )
    (net (code "81") (name "unconnected-(U4-PC14{slash}OSC32_IN-Pad8)") (class "Default")
      (node (ref "U4") (pin "8") (pinfunction "PC14/OSC32_IN_8") (pintype "bidirectional"))
    )
    (net (code "82") (name "unconnected-(U4-PC15{slash}OSC32_OUT-Pad9)") (class "Default")
      (node (ref "U4") (pin "9") (pinfunction "PC15/OSC32_OUT_9") (pintype "bidirectional"))
    )
    (net (code "83") (name "unconnected-(U4-PD0{slash}FSMC_D2{slash}CAN1_RX-Pad81)") (class "Default")
      (node (ref "U4") (pin "81") (pinfunction "PD0/FSMC_D2/CAN1_RX_81") (pintype "bidirectional"))
    )
    (net (code "84") (name "unconnected-(U4-PD1FSMC_D3{slash}CAN1_TX-Pad82)") (class "Default")
      (node (ref "U4") (pin "82") (pinfunction "PD1FSMC_D3/CAN1_TX_82") (pintype "bidirectional"))
    )
    (net (code "85") (name "unconnected-(U4-PD2{slash}TIM3_ETR{slash}UART5_RXSDIO_CMD{slash}DCMI_D11-Pad83)") (class "Default")
      (node (ref "U4") (pin "83") (pinfunction "PD2/TIM3_ETR/UART5_RXSDIO_CMD/DCMI_D11_83") (pintype "bidirectional"))
    )
    (net (code "86") (name "unconnected-(U4-PD3{slash}FSMC_CLK{slash}USART2_CTS-Pad84)") (class "Default")
      (node (ref "U4") (pin "84") (pinfunction "PD3/FSMC_CLK/USART2_CTS_84") (pintype "bidirectional"))
    )
    (net (code "87") (name "unconnected-(U4-PD7{slash}USART2_CK{slash}FSMC_NE1{slash}FSMC_NCE2-Pad88)") (class "Default")
      (node (ref "U4") (pin "88") (pinfunction "PD7/USART2_CK/FSMC_NE1/FSMC_NCE2_88") (pintype "bidirectional"))
    )
    (net (code "88") (name "unconnected-(U4-PD10{slash}FSMC_D15{slash}USART3_CK-Pad57)") (class "Default")
      (node (ref "U4") (pin "57") (pinfunction "PD10/FSMC_D15/USART3_CK_57") (pintype "bidirectional"))
    )
    (net (code "89") (name "unconnected-(U4-PD11{slash}FSMC_A16{slash}USART3_CTS-Pad58)") (class "Default")
      (node (ref "U4") (pin "58") (pinfunction "PD11/FSMC_A16/USART3_CTS_58") (pintype "bidirectional"))
    )
    (net (code "90") (name "unconnected-(U4-PD12{slash}FSMC_A17{slash}TIM4_CH1{slash}USART3_RTS-Pad59)") (class "Default")
      (node (ref "U4") (pin "59") (pinfunction "PD12/FSMC_A17/TIM4_CH1/USART3_RTS_59") (pintype "bidirectional"))
    )
    (net (code "91") (name "unconnected-(U4-PD13{slash}FSMC_A18{slash}TIM4_CH2-Pad60)") (class "Default")
      (node (ref "U4") (pin "60") (pinfunction "PD13/FSMC_A18/TIM4_CH2_60") (pintype "bidirectional"))
    )
    (net (code "92") (name "unconnected-(U4-PD14{slash}FSMC_D0{slash}TIM4_CH3-Pad61)") (class "Default")
      (node (ref "U4") (pin "61") (pinfunction "PD14/FSMC_D0/TIM4_CH3_61") (pintype "bidirectional"))
    )
    (net (code "93") (name "unconnected-(U4-PD15{slash}FSMC_D1{slash}TIM4_CH4-Pad62)") (class "Default")
      (node (ref "U4") (pin "62") (pinfunction "PD15/FSMC_D1/TIM4_CH4_62") (pintype "bidirectional"))
    )
    (net (code "94") (name "unconnected-(U4-PE2{slash}TRACECLK{slash}FSMC_A23{slash}ETH_MII_TXD3-Pad1)") (class "Default")
      (node (ref "U4") (pin "1") (pinfunction "PE2/TRACECLK/FSMC_A23/ETH_MII_TXD3_1") (pintype "bidirectional"))
    )
    (net (code "95") (name "unconnected-(U4-PE3{slash}TRACED0{slash}FSMC_A19-Pad2)") (class "Default")
      (node (ref "U4") (pin "2") (pinfunction "PE3/TRACED0/FSMC_A19_2") (pintype "bidirectional"))
    )
    (net (code "96") (name "unconnected-(U4-PE7{slash}FSMC_D4{slash}TIM1_ETR-Pad38)") (class "Default")
      (node (ref "U4") (pin "38") (pinfunction "PE7/FSMC_D4/TIM1_ETR_38") (pintype "bidirectional"))
    )
    (net (code "97") (name "unconnected-(U4-PE8{slash}FSMC_D5{slash}TIM1_CH1N-Pad39)") (class "Default")
      (node (ref "U4") (pin "39") (pinfunction "PE8/FSMC_D5/TIM1_CH1N_39") (pintype "bidirectional"))
    )
    (net (code "98") (name "unconnected-(U4-PE10{slash}FSMC_D7{slash}TIM1_CH2N-Pad41)") (class "Default")
      (node (ref "U4") (pin "41") (pinfunction "PE10/FSMC_D7/TIM1_CH2N_41") (pintype "bidirectional"))
    )
    (net (code "99") (name "unconnected-(U4-PE11{slash}FSMC_D8{slash}TIM1_CH2-Pad42)") (class "Default")
      (node (ref "U4") (pin "42") (pinfunction "PE11/FSMC_D8/TIM1_CH2_42") (pintype "bidirectional"))
    )
    (net (code "100") (name "unconnected-(U4-PE12{slash}FSMC_D9{slash}TIM1_CH3N-Pad43)") (class "Default")
      (node (ref "U4") (pin "43") (pinfunction "PE12/FSMC_D9/TIM1_CH3N_43") (pintype "bidirectional"))
    )
    (net (code "101") (name "unconnected-(U4-PE13{slash}FSMC_D10{slash}TIM1_CH3-Pad44)") (class "Default")
      (node (ref "U4") (pin "44") (pinfunction "PE13/FSMC_D10/TIM1_CH3_44") (pintype "bidirectional"))
    )
    (net (code "102") (name "unconnected-(U4-PE14{slash}FSMC_D11{slash}TIM1_CH4-Pad45)") (class "Default")
      (node (ref "U4") (pin "45") (pinfunction "PE14/FSMC_D11/TIM1_CH4_45") (pintype "bidirectional"))
    )
    (net (code "103") (name "unconnected-(U4-PE15FSMC_D12{slash}TIM1_BKIN-Pad46)") (class "Default")
      (node (ref "U4") (pin "46") (pinfunction "PE15FSMC_D12/TIM1_BKIN_46") (pintype "bidirectional"))
    )
  )
)
